# Main_MCU.net
KiCad netlist of a schematic drawn in Altium Designer
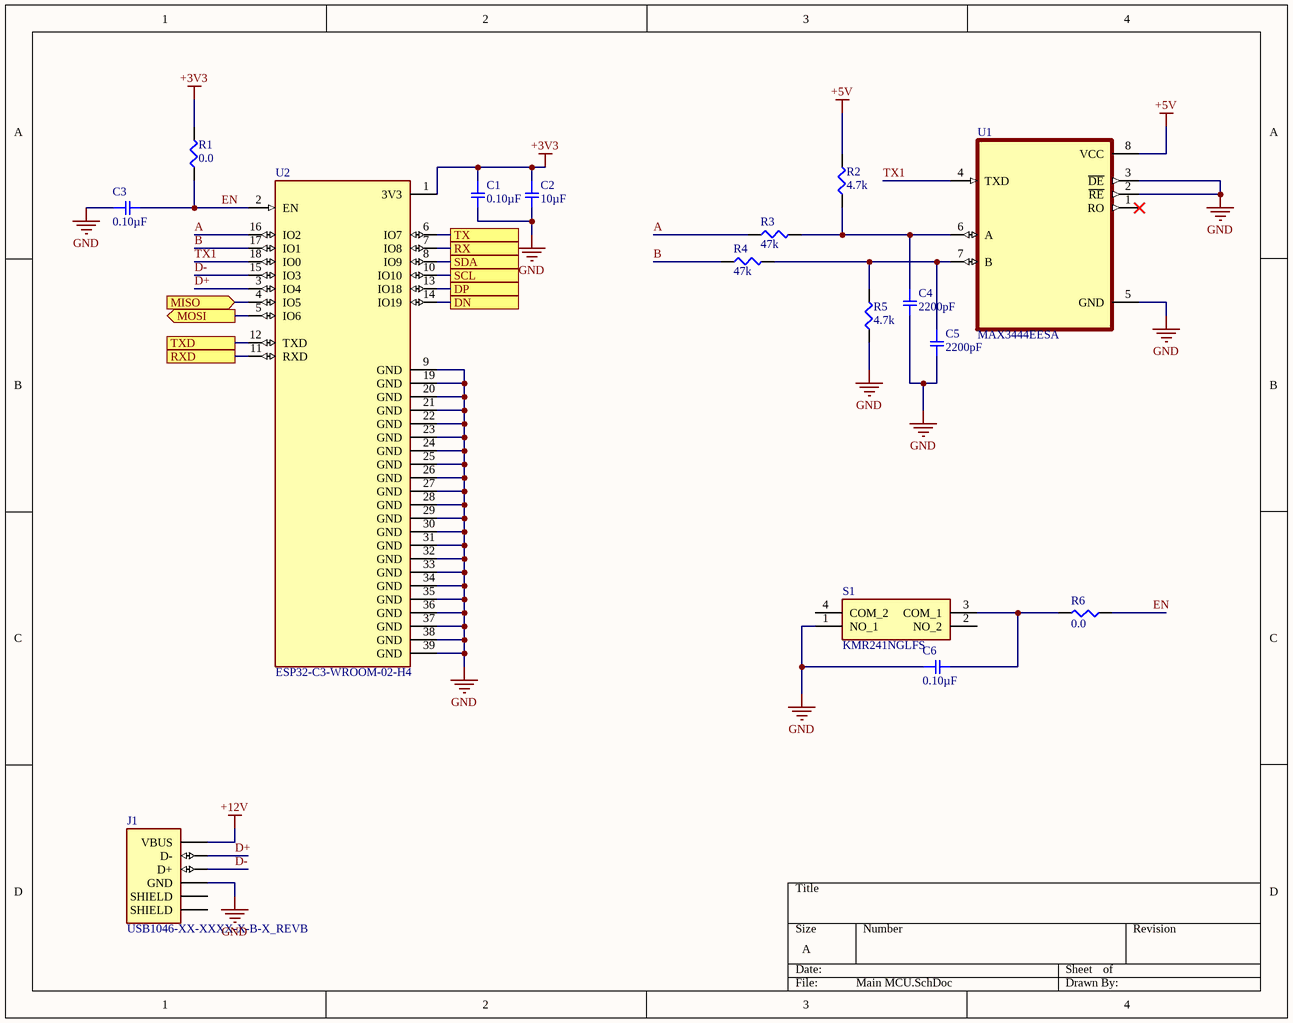
[diagram p0: Main MCU.SchDoc]

(export (version "E")
  (design (tool "Eeschema 10.0.6"))
  (components
    (comp (ref "C1")
      (value "0.10µF")
      (footprint "SMD-0402C")
      (description "CAP CER 0.1UF 16V X7R 0402")
      (fields
        (field (name "DIGI-KEY PART NUMBER") "490-4759-1-ND")
        (field (name "PART NUMBER") "GCM155R71C104KA55D")
      )
      (libsource (lib "capacitor_murata_0402") (part "GCM155R71C104KA55D"))
    )
    (comp (ref "C2")
      (value "10µF")
      (footprint "SMD-0402C")
      (description "CAP CER 10UF 6.3V X5R 0402")
      (fields
        (field (name "DIGI-KEY PART NUMBER") "490-13211-1-ND")
        (field (name "PART NUMBER") "GRJ155R60J106ME11D")
      )
      (libsource (lib "capacitor_murata_0402") (part "GRJ155R60J106ME11D"))
    )
    (comp (ref "C3")
      (value "0.10µF")
      (footprint "SMD-0402C")
      (description "CAP CER 0.1UF 16V X7R 0402")
      (fields
        (field (name "DIGI-KEY PART NUMBER") "490-4759-1-ND")
        (field (name "PART NUMBER") "GCM155R71C104KA55D")
      )
      (libsource (lib "capacitor_murata_0402") (part "GCM155R71C104KA55D"))
    )
    (comp (ref "C4")
      (value "2200pF")
      (footprint "SMD-0402C")
      (description "CAP CER 2200PF 50V X7R 0402")
      (fields
        (field (name "DIGI-KEY PART NUMBER") "490-4914-1-ND")
        (field (name "PART NUMBER") "GCM155R71H222KA37D")
      )
      (libsource (lib "capacitor_murata_0402") (part "GCM155R71H222KA37D"))
    )
    (comp (ref "C5")
      (value "2200pF")
      (footprint "SMD-0402C")
      (description "CAP CER 2200PF 50V X7R 0402")
      (fields
        (field (name "DIGI-KEY PART NUMBER") "490-4914-1-ND")
        (field (name "PART NUMBER") "GCM155R71H222KA37D")
      )
      (libsource (lib "capacitor_murata_0402") (part "GCM155R71H222KA37D"))
    )
    (comp (ref "C6")
      (value "0.10µF")
      (footprint "SMD-0402C")
      (description "CAP CER 0.1UF 16V X7R 0402")
      (fields
        (field (name "DIGI-KEY PART NUMBER") "490-4759-1-ND")
        (field (name "PART NUMBER") "GCM155R71C104KA55D")
      )
      (libsource (lib "capacitor_murata_0402") (part "GCM155R71C104KA55D"))
    )
    (comp (ref "J1")
      (value "USB1046-XX-XXXX-X-B-X_REVB")
      (footprint "USB1046-GF-0190-L-B-A:GCT_USB1046-XX-XXXX-X-B-X_REVB")
      (description "USB Receptacle, Type A, 4 Pin, Surface Mount, Horizontal, Top Mount, with Shell Stakes")
      (fields (field (name "MF") "{'manufacturer': u'Global Connector Technology'}"))
      (libsource (lib "*") (part "USB1046-XX-XXXX-X-B-X_REVB"))
    )
    (comp (ref "R1")
      (value "0.0")
      (footprint "SMD-0402-RES")
      (description "RES SMD 0.0OHM JUMPER 1/10W 0402")
      (fields (field (name "PART NUMBER") "ERJ-2GE0R00X") (field (name "DIGI-KEY PART NUMBER") "P0.0JCT-ND"))
      (libsource (lib "Panasonic_ERJ_0402") (part "ERJ-2GE0R00X"))
    )
    (comp (ref "R2")
      (value "4.7k")
      (footprint "SMD-0402-RES")
      (description "RES SMD 4.7K OHM 5% 1/10W 0402")
      (fields (field (name "PART NUMBER") "ERJ-2GEJ472X") (field (name "DIGI-KEY PART NUMBER") "P4.7KJCT-ND"))
      (libsource (lib "Panasonic_ERJ_0402") (part "ERJ-2GEJ472X"))
    )
    (comp (ref "R3")
      (value "47k")
      (footprint "SMD-0402-RES")
      (description "RES SMD 47K OHM 5% 1/10W 0402")
      (fields (field (name "PART NUMBER") "ERJ-2GEJ473X") (field (name "DIGI-KEY PART NUMBER") "P47KJCT-ND"))
      (libsource (lib "Panasonic_ERJ_0402") (part "ERJ-2GEJ473X"))
    )
    (comp (ref "R4")
      (value "47k")
      (footprint "SMD-0402-RES")
      (description "RES SMD 47K OHM 5% 1/10W 0402")
      (fields (field (name "PART NUMBER") "ERJ-2GEJ473X") (field (name "DIGI-KEY PART NUMBER") "P47KJCT-ND"))
      (libsource (lib "Panasonic_ERJ_0402") (part "ERJ-2GEJ473X"))
    )
    (comp (ref "R5")
      (value "4.7k")
      (footprint "SMD-0402-RES")
      (description "RES SMD 4.7K OHM 5% 1/10W 0402")
      (fields (field (name "PART NUMBER") "ERJ-2GEJ472X") (field (name "DIGI-KEY PART NUMBER") "P4.7KJCT-ND"))
      (libsource (lib "Panasonic_ERJ_0402") (part "ERJ-2GEJ472X"))
    )
    (comp (ref "R6")
      (value "0.0")
      (footprint "SMD-0402-RES")
      (description "RES SMD 0.0OHM JUMPER 1/10W 0402")
      (fields (field (name "PART NUMBER") "ERJ-2GE0R00X") (field (name "DIGI-KEY PART NUMBER") "P0.0JCT-ND"))
      (libsource (lib "Panasonic_ERJ_0402") (part "ERJ-2GE0R00X"))
    )
    (comp (ref "S1")
      (value "KMR241NGLFS")
      (footprint "SamacSys:KMR241NGLFS")
      (description "Switch")
      (fields (field (name "MOUSER PART NUMBER") "611-KMR241NGLFS"))
      (libsource (lib "SamacSys") (part "KMR241NGLFS"))
    )
    (comp (ref "U1")
      (value "MAX3444EESA")
      (footprint "MAX3444EESA:SOIC127P600X175-8N")
      (fields (field (name "MF") "{'manufacturer': u'Analog Devices'}"))
      (libsource (lib "*") (part "MAX3444EESA"))
    )
    (comp (ref "U2")
      (value "ESP32-C3-WROOM-02-H4")
      (footprint "ESP32-C3-WROOM-02-H4:MODULE_ESP32-C3-WROOM-02-H4")
      (fields (field (name "MF") "{'manufacturer': u'Espressif Systems'}"))
      (libsource (lib "*") (part "ESP32-C3-WROOM-02-H4"))
    )
  )
  (nets
    (net (code "1") (name "+3V3") (class "Default")
      (node (ref "C1") (pin "1") (pinfunction "1_1") (pintype "passive"))
      (node (ref "C2") (pin "1") (pinfunction "1_1") (pintype "passive"))
      (node (ref "R1") (pin "2") (pinfunction "2_2") (pintype "passive"))
      (node (ref "U2") (pin "1") (pinfunction "3V3_1") (pintype "power_in"))
    )
    (net (code "2") (name "+5V") (class "Default")
      (node (ref "R2") (pin "2") (pinfunction "2_2") (pintype "passive"))
      (node (ref "U1") (pin "8") (pinfunction "VCC_8") (pintype "power_in"))
    )
    (net (code "3") (name "+12V") (class "Default")
      (node (ref "J1") (pin "1") (pinfunction "VBUS_1") (pintype "power_in"))
    )
    (net (code "4") (name "/A") (class "Default")
      (node (ref "R3") (pin "1") (pinfunction "1_1") (pintype "passive"))
      (node (ref "U2") (pin "16") (pinfunction "IO2_16") (pintype "bidirectional"))
    )
    (net (code "5") (name "/B") (class "Default")
      (node (ref "R4") (pin "1") (pinfunction "1_1") (pintype "passive"))
      (node (ref "U2") (pin "17") (pinfunction "IO1_17") (pintype "bidirectional"))
    )
    (net (code "6") (name "/D+") (class "Default")
      (node (ref "J1") (pin "2") (pinfunction "D-_2") (pintype "bidirectional"))
      (node (ref "U2") (pin "3") (pinfunction "IO4_3") (pintype "bidirectional"))
    )
    (net (code "7") (name "/D-") (class "Default")
      (node (ref "J1") (pin "3") (pinfunction "D+_3") (pintype "bidirectional"))
      (node (ref "U2") (pin "15") (pinfunction "IO3_15") (pintype "bidirectional"))
    )
    (net (code "8") (name "/DN") (class "Default")
      (node (ref "U2") (pin "14") (pinfunction "IO19_14") (pintype "bidirectional"))
    )
    (net (code "9") (name "/DP") (class "Default")
      (node (ref "U2") (pin "13") (pinfunction "IO18_13") (pintype "bidirectional"))
    )
    (net (code "10") (name "/EN") (class "Default")
      (node (ref "C3") (pin "2") (pinfunction "2_2") (pintype "passive"))
      (node (ref "R1") (pin "1") (pinfunction "1_1") (pintype "passive"))
      (node (ref "R6") (pin "1") (pinfunction "1_1") (pintype "passive"))
      (node (ref "U2") (pin "2") (pinfunction "EN_2") (pintype "input"))
    )
    (net (code "11") (name "/MISO") (class "Default")
      (node (ref "U2") (pin "4") (pinfunction "IO5_4") (pintype "bidirectional"))
    )
    (net (code "12") (name "/MOSI") (class "Default")
      (node (ref "U2") (pin "5") (pinfunction "IO6_5") (pintype "bidirectional"))
    )
    (net (code "13") (name "/RX") (class "Default")
      (node (ref "U2") (pin "7") (pinfunction "IO8_7") (pintype "bidirectional"))
    )
    (net (code "14") (name "/RXD") (class "Default")
      (node (ref "U2") (pin "11") (pinfunction "RXD_11") (pintype "bidirectional"))
    )
    (net (code "15") (name "/SCL") (class "Default")
      (node (ref "U2") (pin "10") (pinfunction "IO10_10") (pintype "bidirectional"))
    )
    (net (code "16") (name "/SDA") (class "Default")
      (node (ref "U2") (pin "8") (pinfunction "IO9_8") (pintype "bidirectional"))
    )
    (net (code "17") (name "/TX") (class "Default")
      (node (ref "U2") (pin "6") (pinfunction "IO7_6") (pintype "bidirectional"))
    )
    (net (code "18") (name "/TX1") (class "Default")
      (node (ref "U1") (pin "4") (pinfunction "TXD_4") (pintype "input"))
      (node (ref "U2") (pin "18") (pinfunction "IO0_18") (pintype "bidirectional"))
    )
    (net (code "19") (name "/TXD") (class "Default")
      (node (ref "U2") (pin "12") (pinfunction "TXD_12") (pintype "bidirectional"))
    )
    (net (code "20") (name "GND") (class "Default")
      (node (ref "C1") (pin "2") (pinfunction "2_2") (pintype "passive"))
      (node (ref "C2") (pin "2") (pinfunction "2_2") (pintype "passive"))
      (node (ref "C3") (pin "1") (pinfunction "1_1") (pintype "passive"))
      (node (ref "C4") (pin "2") (pinfunction "2_2") (pintype "passive"))
      (node (ref "C5") (pin "2") (pinfunction "2_2") (pintype "passive"))
      (node (ref "C6") (pin "1") (pinfunction "1_1") (pintype "passive"))
      (node (ref "J1") (pin "4") (pinfunction "GND_4") (pintype "power_in"))
      (node (ref "R5") (pin "1") (pinfunction "1_1") (pintype "passive"))
      (node (ref "S1") (pin "1") (pinfunction "NO_1_1") (pintype "passive"))
      (node (ref "U1") (pin "2") (pinfunction "~{RE}_2") (pintype "output"))
      (node (ref "U1") (pin "3") (pinfunction "~{DE}_3") (pintype "output"))
      (node (ref "U1") (pin "5") (pinfunction "GND_5") (pintype "power_in"))
      (node (ref "U2") (pin "19") (pinfunction "GND_19") (pintype "power_in"))
      (node (ref "U2") (pin "20") (pinfunction "GND_20") (pintype "power_in"))
      (node (ref "U2") (pin "21") (pinfunction "GND_21") (pintype "power_in"))
      (node (ref "U2") (pin "22") (pinfunction "GND_22") (pintype "power_in"))
      (node (ref "U2") (pin "23") (pinfunction "GND_23") (pintype "power_in"))
      (node (ref "U2") (pin "24") (pinfunction "GND_24") (pintype "power_in"))
      (node (ref "U2") (pin "25") (pinfunction "GND_25") (pintype "power_in"))
      (node (ref "U2") (pin "26") (pinfunction "GND_26") (pintype "power_in"))
      (node (ref "U2") (pin "27") (pinfunction "GND_27") (pintype "power_in"))
      (node (ref "U2") (pin "28") (pinfunction "GND_28") (pintype "power_in"))
      (node (ref "U2") (pin "29") (pinfunction "GND_29") (pintype "power_in"))
      (node (ref "U2") (pin "30") (pinfunction "GND_30") (pintype "power_in"))
      (node (ref "U2") (pin "31") (pinfunction "GND_31") (pintype "power_in"))
      (node (ref "U2") (pin "32") (pinfunction "GND_32") (pintype "power_in"))
      (node (ref "U2") (pin "33") (pinfunction "GND_33") (pintype "power_in"))
      (node (ref "U2") (pin "34") (pinfunction "GND_34") (pintype "power_in"))
      (node (ref "U2") (pin "35") (pinfunction "GND_35") (pintype "power_in"))
      (node (ref "U2") (pin "36") (pinfunction "GND_36") (pintype "power_in"))
      (node (ref "U2") (pin "37") (pinfunction "GND_37") (pintype "power_in"))
      (node (ref "U2") (pin "38") (pinfunction "GND_38") (pintype "power_in"))
      (node (ref "U2") (pin "39") (pinfunction "GND_39") (pintype "power_in"))
      (node (ref "U2") (pin "9") (pinfunction "GND_9") (pintype "power_in"))
    )
    (net (code "21") (name "Net-(S1-COM_1)") (class "Default")
      (node (ref "C6") (pin "2") (pinfunction "2_2") (pintype "passive"))
      (node (ref "R6") (pin "2") (pinfunction "2_2") (pintype "passive"))
      (node (ref "S1") (pin "3") (pinfunction "COM_1_3") (pintype "passive"))
    )
    (net (code "22") (name "Net-(U1-A)") (class "Default")
      (node (ref "C4") (pin "1") (pinfunction "1_1") (pintype "passive"))
      (node (ref "R2") (pin "1") (pinfunction "1_1") (pintype "passive"))
      (node (ref "R3") (pin "2") (pinfunction "2_2") (pintype "passive"))
      (node (ref "U1") (pin "6") (pinfunction "A_6") (pintype "bidirectional"))
    )
    (net (code "23") (name "Net-(U1-B)") (class "Default")
      (node (ref "C5") (pin "1") (pinfunction "1_1") (pintype "passive"))
      (node (ref "R4") (pin "2") (pinfunction "2_2") (pintype "passive"))
      (node (ref "R5") (pin "2") (pinfunction "2_2") (pintype "passive"))
      (node (ref "U1") (pin "7") (pinfunction "B_7") (pintype "bidirectional"))
    )
    (net (code "24") (name "unconnected-(J1-SHIELD-PadP1)") (class "Default")
      (node (ref "J1") (pin "P1") (pinfunction "SHIELD_P1") (pintype "power_in"))
    )
    (net (code "25") (name "unconnected-(J1-SHIELD-PadP2)") (class "Default")
      (node (ref "J1") (pin "P2") (pinfunction "SHIELD_P2") (pintype "power_in"))
    )
    (net (code "26") (name "unconnected-(S1-COM_2-Pad4)") (class "Default")
      (node (ref "S1") (pin "4") (pinfunction "COM_2_4") (pintype "passive"))
    )
    (net (code "27") (name "unconnected-(S1-NO_2-Pad2)") (class "Default")
      (node (ref "S1") (pin "2") (pinfunction "NO_2_2") (pintype "passive"))
    )
    (net (code "28") (name "unconnected-(U1-RO-Pad1)") (class "Default")
      (node (ref "U1") (pin "1") (pinfunction "RO_1") (pintype "output+no_connect"))
    )
  )
)
